# 8266_DIYIOT_Board_K_G_V_SDA_SCL.net
KiCad netlist of a schematic drawn in EAGLE
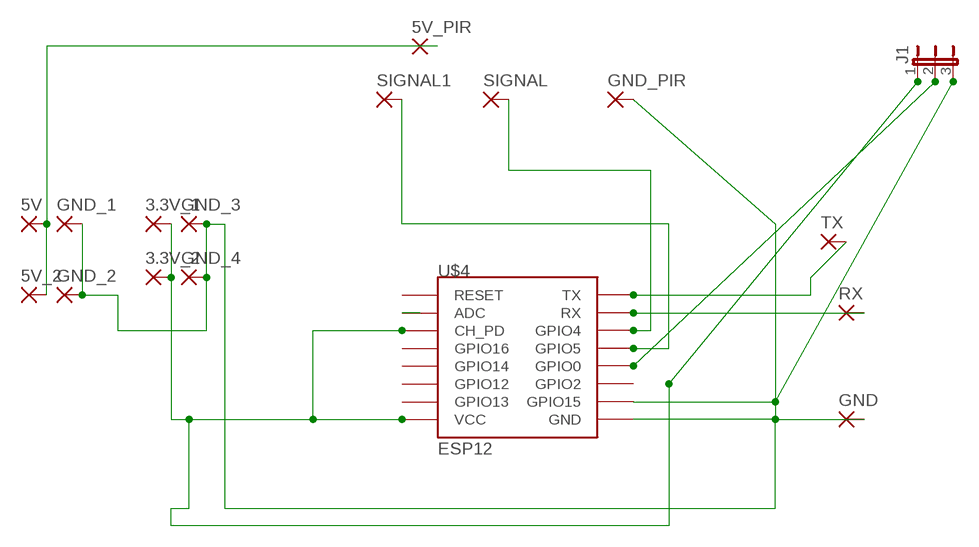
[diagram p0: schematic, sheet 1]

(export (version "E")
  (design (tool "Eeschema 10.0.6"))
  (components
    (comp (ref "3.3V_1")
      (value "2,15/1,0")
      (footprint "eagle-import:2,15_1,0")
      (libsource (lib "eagle-import") (part "2,15/1,0"))
    )
    (comp (ref "3.3V_2")
      (value "2,15/1,0")
      (footprint "eagle-import:2,15_1,0")
      (libsource (lib "eagle-import") (part "2,15/1,0"))
    )
    (comp (ref "5V")
      (value "2,15/1,0")
      (footprint "eagle-import:2,15_1,0")
      (libsource (lib "eagle-import") (part "2,15/1,0"))
    )
    (comp (ref "5V_2")
      (value "2,15/1,0")
      (footprint "eagle-import:2,15_1,0")
      (libsource (lib "eagle-import") (part "2,15/1,0"))
    )
    (comp (ref "5V_PIR")
      (value "2,15/1,0")
      (footprint "eagle-import:2,15_1,0")
      (libsource (lib "eagle-import") (part "2,15/1,0"))
    )
    (comp (ref "GND")
      (value "2,15/1,0")
      (footprint "eagle-import:2,15_1,0")
      (libsource (lib "eagle-import") (part "2,15/1,0"))
    )
    (comp (ref "GND_1")
      (value "2,15/1,0")
      (footprint "eagle-import:2,15_1,0")
      (libsource (lib "eagle-import") (part "2,15/1,0"))
    )
    (comp (ref "GND_2")
      (value "2,15/1,0")
      (footprint "eagle-import:2,15_1,0")
      (libsource (lib "eagle-import") (part "2,15/1,0"))
    )
    (comp (ref "GND_3")
      (value "2,15/1,0")
      (footprint "eagle-import:2,15_1,0")
      (libsource (lib "eagle-import") (part "2,15/1,0"))
    )
    (comp (ref "GND_4")
      (value "2,15/1,0")
      (footprint "eagle-import:2,15_1,0")
      (libsource (lib "eagle-import") (part "2,15/1,0"))
    )
    (comp (ref "GND_PIR")
      (value "2,15/1,0")
      (footprint "eagle-import:2,15_1,0")
      (libsource (lib "eagle-import") (part "2,15/1,0"))
    )
    (comp (ref "J1")
      (value "JP2E")
      (footprint "eagle-import:JP2")
      (libsource (lib "eagle-import") (part "JP2E"))
    )
    (comp (ref "RX")
      (value "2,15/1,0")
      (footprint "eagle-import:2,15_1,0")
      (libsource (lib "eagle-import") (part "2,15/1,0"))
    )
    (comp (ref "SIGNAL")
      (value "2,15/1,0")
      (footprint "eagle-import:2,15_1,0")
      (libsource (lib "eagle-import") (part "2,15/1,0"))
    )
    (comp (ref "SIGNAL1")
      (value "2,15/1,0")
      (footprint "eagle-import:2,15_1,0")
      (libsource (lib "eagle-import") (part "2,15/1,0"))
    )
    (comp (ref "TX")
      (value "2,15/1,0")
      (footprint "eagle-import:2,15_1,0")
      (libsource (lib "eagle-import") (part "2,15/1,0"))
    )
    (comp (ref "U$4")
      (value "ESP12")
      (footprint "eagle-import:ESP12")
      (libsource (lib "eagle-import") (part "ESP12"))
    )
  )
  (nets
    (net (code "1") (name "/5V") (class "Default")
      (node (ref "5V") (pin "1") (pinfunction "P_1") (pintype "passive"))
      (node (ref "5V_2") (pin "1") (pinfunction "P_1") (pintype "passive"))
      (node (ref "5V_PIR") (pin "1") (pinfunction "P_1") (pintype "passive"))
      (node (ref "GND") (pin "1") (pinfunction "P_1") (pintype "passive"))
      (node (ref "GND_1") (pin "1") (pinfunction "P_1") (pintype "passive"))
      (node (ref "GND_2") (pin "1") (pinfunction "P_1") (pintype "passive"))
      (node (ref "GND_3") (pin "1") (pinfunction "P_1") (pintype "passive"))
      (node (ref "GND_4") (pin "1") (pinfunction "P_1") (pintype "passive"))
      (node (ref "GND_PIR") (pin "1") (pinfunction "P_1") (pintype "passive"))
      (node (ref "J1") (pin "3") (pinfunction "3_3") (pintype "passive"))
      (node (ref "U$4") (pin "GND") (pinfunction "GND_GND") (pintype "bidirectional"))
      (node (ref "U$4") (pin "GPIO15") (pinfunction "GPIO15_GPIO15") (pintype "bidirectional"))
    )
    (net (code "2") (name "Net-(3.3V_1-P)") (class "Default")
      (node (ref "3.3V_1") (pin "1") (pinfunction "P_1") (pintype "passive"))
      (node (ref "3.3V_2") (pin "1") (pinfunction "P_1") (pintype "passive"))
      (node (ref "J1") (pin "1") (pinfunction "1_1") (pintype "passive"))
      (node (ref "U$4") (pin "CH_PD") (pinfunction "CH_PD_CH_PD") (pintype "bidirectional"))
      (node (ref "U$4") (pin "VCC") (pinfunction "VCC_VCC") (pintype "bidirectional"))
    )
    (net (code "3") (name "Net-(J1-Pad2)") (class "Default")
      (node (ref "J1") (pin "2") (pinfunction "2_2") (pintype "passive"))
      (node (ref "U$4") (pin "GPIO0") (pinfunction "GPIO0_GPIO0") (pintype "bidirectional"))
    )
    (net (code "4") (name "Net-(RX-P)") (class "Default")
      (node (ref "RX") (pin "1") (pinfunction "P_1") (pintype "passive"))
      (node (ref "U$4") (pin "RX") (pinfunction "RX_RX") (pintype "bidirectional"))
    )
    (net (code "5") (name "Net-(SIGNAL-P)") (class "Default")
      (node (ref "SIGNAL") (pin "1") (pinfunction "P_1") (pintype "passive"))
      (node (ref "U$4") (pin "GPIO4") (pinfunction "GPIO4_GPIO4") (pintype "bidirectional"))
    )
    (net (code "6") (name "Net-(SIGNAL1-P)") (class "Default")
      (node (ref "SIGNAL1") (pin "1") (pinfunction "P_1") (pintype "passive"))
      (node (ref "U$4") (pin "GPIO5") (pinfunction "GPIO5_GPIO5") (pintype "bidirectional"))
    )
    (net (code "7") (name "Net-(TX-P)") (class "Default")
      (node (ref "TX") (pin "1") (pinfunction "P_1") (pintype "passive"))
      (node (ref "U$4") (pin "TX") (pinfunction "TX_TX") (pintype "bidirectional"))
    )
    (net (code "8") (name "unconnected-(U$4-PadADC)") (class "Default")
      (node (ref "U$4") (pin "ADC") (pinfunction "ADC_ADC") (pintype "bidirectional"))
    )
    (net (code "9") (name "unconnected-(U$4-PadGPIO2)") (class "Default")
      (node (ref "U$4") (pin "GPIO2") (pinfunction "GPIO2_GPIO2") (pintype "bidirectional"))
    )
    (net (code "10") (name "unconnected-(U$4-PadGPIO12)") (class "Default")
      (node (ref "U$4") (pin "GPIO12") (pinfunction "GPIO12_GPIO12") (pintype "bidirectional"))
    )
    (net (code "11") (name "unconnected-(U$4-PadGPIO13)") (class "Default")
      (node (ref "U$4") (pin "GPIO13") (pinfunction "GPIO13_GPIO13") (pintype "bidirectional"))
    )
    (net (code "12") (name "unconnected-(U$4-PadGPIO14)") (class "Default")
      (node (ref "U$4") (pin "GPIO14") (pinfunction "GPIO14_GPIO14") (pintype "bidirectional"))
    )
    (net (code "13") (name "unconnected-(U$4-PadGPIO16)") (class "Default")
      (node (ref "U$4") (pin "GPIO16") (pinfunction "GPIO16_GPIO16") (pintype "bidirectional"))
    )
    (net (code "14") (name "unconnected-(U$4-PadRESET)") (class "Default")
      (node (ref "U$4") (pin "RESET") (pinfunction "RESET_RESET") (pintype "bidirectional"))
    )
  )
)
